# Modulo_MotorDC.net
KiCad netlist of a schematic drawn in Altium Designer
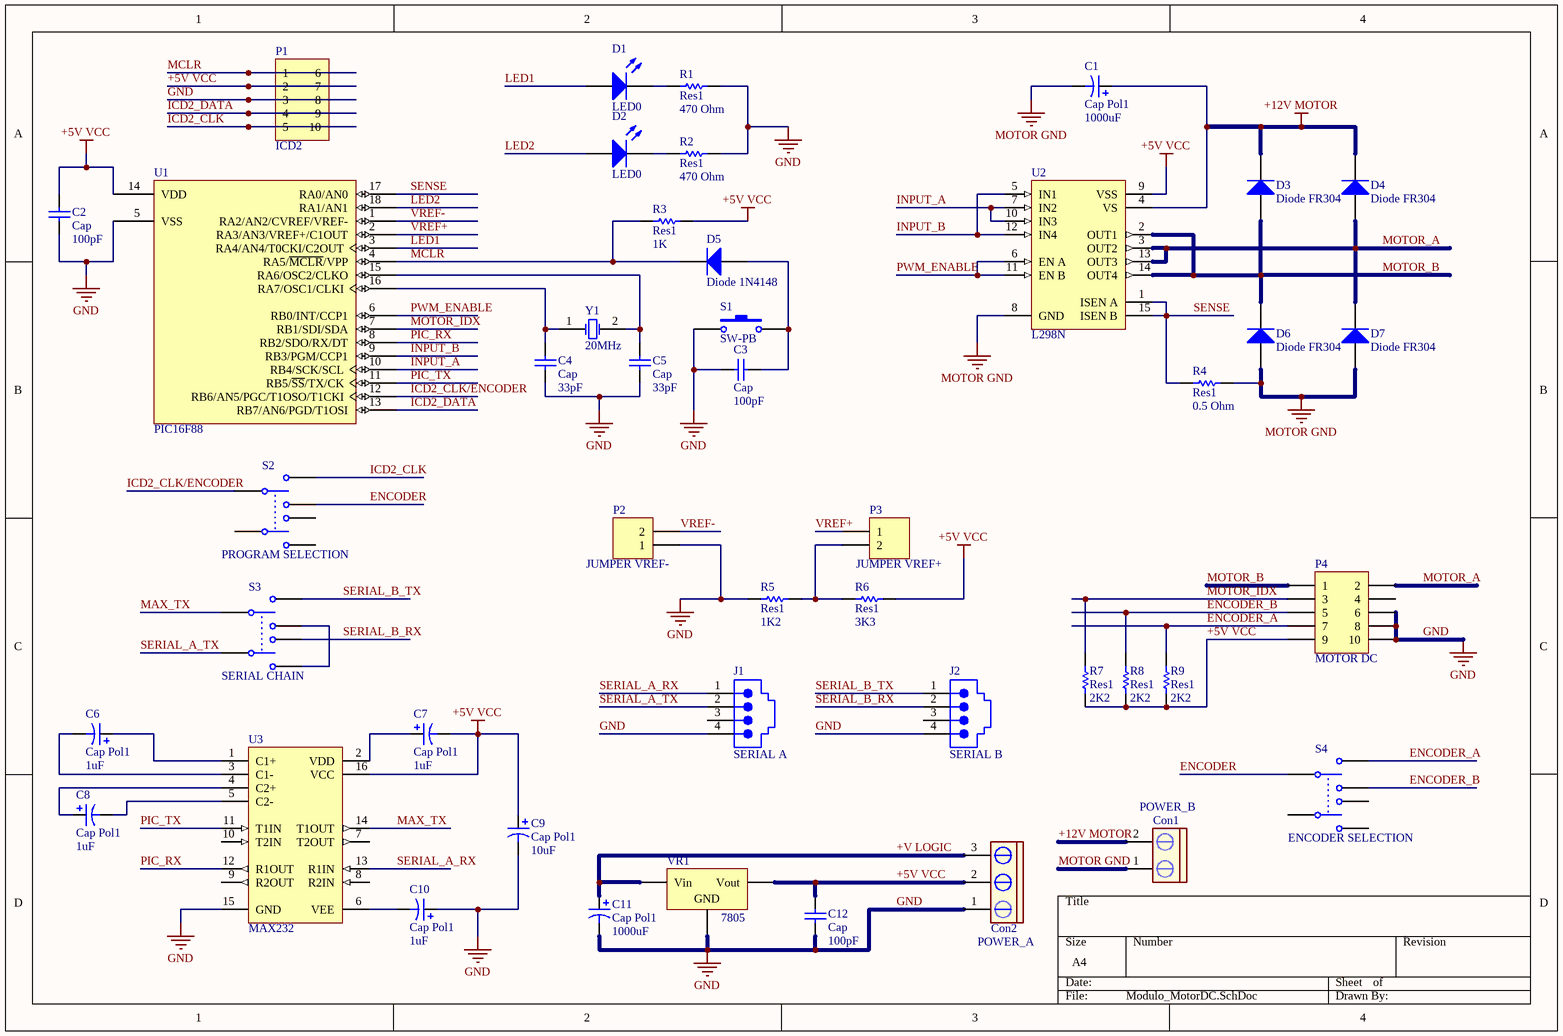
[diagram p0: Modulo_MotorDC.SchDoc]

(export (version "E")
  (design (tool "Eeschema 10.0.6"))
  (components
    (comp (ref "C1")
      (value "Cap Pol1")
      (footprint "RB5-10.5")
      (description "Polarized Capacitor (Radial)")
      (fields (field (name "ALTIUM_VALUE") "1000uF") (field (name "PUBLISHER") "Altium Limited"))
      (libsource (lib "Miscellaneous Devices") (part "Cap Pol1"))
    )
    (comp (ref "C2")
      (value "Cap")
      (footprint "CAPR2.54-5.1x3.2")
      (description "Capacitor")
      (fields (field (name "ALTIUM_VALUE") "100pF") (field (name "PUBLISHER") "Altium Limited"))
      (libsource (lib "Miscellaneous Devices") (part "Cap"))
    )
    (comp (ref "C3")
      (value "Cap")
      (footprint "CAPR2.54-5.1x3.2")
      (description "Capacitor")
      (fields (field (name "ALTIUM_VALUE") "100pF") (field (name "PUBLISHER") "Altium Limited"))
      (libsource (lib "Miscellaneous Devices") (part "Cap"))
    )
    (comp (ref "C4")
      (value "Cap")
      (footprint "CAPR2.54-5.1x3.2")
      (description "Capacitor")
      (fields (field (name "ALTIUM_VALUE") "33pF") (field (name "PUBLISHER") "Altium Limited"))
      (libsource (lib "Miscellaneous Devices") (part "Cap"))
    )
    (comp (ref "C5")
      (value "Cap")
      (footprint "CAPR2.54-5.1x3.2")
      (description "Capacitor")
      (fields (field (name "ALTIUM_VALUE") "33pF") (field (name "PUBLISHER") "Altium Limited"))
      (libsource (lib "Miscellaneous Devices") (part "Cap"))
    )
    (comp (ref "C6")
      (value "Cap Pol1")
      (footprint "CAPPR2-5x6.8")
      (description "Polarized Capacitor (Radial)")
      (fields (field (name "ALTIUM_VALUE") "1uF") (field (name "PUBLISHER") "Altium Limited"))
      (libsource (lib "Miscellaneous Devices") (part "Cap Pol1"))
    )
    (comp (ref "C7")
      (value "Cap Pol1")
      (footprint "CAPPR2-5x6.8")
      (description "Polarized Capacitor (Radial)")
      (fields (field (name "ALTIUM_VALUE") "1uF") (field (name "PUBLISHER") "Altium Limited"))
      (libsource (lib "Miscellaneous Devices") (part "Cap Pol1"))
    )
    (comp (ref "C8")
      (value "Cap Pol1")
      (footprint "CAPPR2-5x6.8")
      (description "Polarized Capacitor (Radial)")
      (fields (field (name "ALTIUM_VALUE") "1uF") (field (name "PUBLISHER") "Altium Limited"))
      (libsource (lib "Miscellaneous Devices") (part "Cap Pol1"))
    )
    (comp (ref "C9")
      (value "Cap Pol1")
      (footprint "CAPPR2-5x6.8")
      (description "Polarized Capacitor (Radial)")
      (fields (field (name "ALTIUM_VALUE") "10uF") (field (name "PUBLISHER") "Altium Limited"))
      (libsource (lib "Miscellaneous Devices") (part "Cap Pol1"))
    )
    (comp (ref "C10")
      (value "Cap Pol1")
      (footprint "CAPPR2-5x6.8")
      (description "Polarized Capacitor (Radial)")
      (fields (field (name "ALTIUM_VALUE") "1uF") (field (name "PUBLISHER") "Altium Limited"))
      (libsource (lib "Miscellaneous Devices") (part "Cap Pol1"))
    )
    (comp (ref "C11")
      (value "Cap Pol1")
      (footprint "RB5-10.5")
      (description "Polarized Capacitor (Radial)")
      (fields (field (name "ALTIUM_VALUE") "1000uF") (field (name "PUBLISHER") "Altium Limited"))
      (libsource (lib "Miscellaneous Devices") (part "Cap Pol1"))
    )
    (comp (ref "C12")
      (value "Cap")
      (footprint "CAPR2.54-5.1x3.2")
      (description "Capacitor")
      (fields (field (name "ALTIUM_VALUE") "100pF") (field (name "PUBLISHER") "Altium Limited"))
      (libsource (lib "Miscellaneous Devices") (part "Cap"))
    )
    (comp (ref "Con1")
      (value "POWER_B")
      (footprint "My_CN2")
      (description "Connector blue screw")
      (libsource (lib "Protel_Library") (part "CON2 pin blue"))
    )
    (comp (ref "Con2")
      (value "POWER_A")
      (footprint "My_CN3")
      (description "Connector green screw")
      (libsource (lib "Protel_Library") (part "CON3 pin Green"))
    )
    (comp (ref "D1")
      (value "LED0")
      (footprint "LED-0")
      (description "Typical INFRARED GaAs LED")
      (fields (field (name "PUBLISHER") "Altium Limited"))
      (libsource (lib "Miscellaneous Devices") (part "LED0"))
    )
    (comp (ref "D2")
      (value "LED0")
      (footprint "LED-0")
      (description "Typical INFRARED GaAs LED")
      (fields (field (name "PUBLISHER") "Altium Limited"))
      (libsource (lib "Miscellaneous Devices") (part "LED0"))
    )
    (comp (ref "D3")
      (value "Diode FR304")
      (footprint "DIO18.84-9.6x5.6")
      (description "3 Amp General Purpose Rectifier")
      (fields (field (name "PUBLISHER") "Altium Limited"))
      (libsource (lib "Miscellaneous Devices") (part "Diode 1N5404"))
    )
    (comp (ref "D4")
      (value "Diode FR304")
      (footprint "DIO18.84-9.6x5.6")
      (description "3 Amp General Purpose Rectifier")
      (fields (field (name "PUBLISHER") "Altium Limited"))
      (libsource (lib "Miscellaneous Devices") (part "Diode 1N5404"))
    )
    (comp (ref "D5")
      (value "Diode 1N4148")
      (footprint "DIO7.1-3.9x1.9")
      (description "High Conductance Fast Diode")
      (fields (field (name "PUBLISHER") "Altium Limited"))
      (libsource (lib "Miscellaneous Devices") (part "Diode 1N4148"))
    )
    (comp (ref "D6")
      (value "Diode FR304")
      (footprint "DIO18.84-9.6x5.6")
      (description "3 Amp General Purpose Rectifier")
      (fields (field (name "PUBLISHER") "Altium Limited"))
      (libsource (lib "Miscellaneous Devices") (part "Diode 1N5404"))
    )
    (comp (ref "D7")
      (value "Diode FR304")
      (footprint "DIO18.84-9.6x5.6")
      (description "3 Amp General Purpose Rectifier")
      (fields (field (name "PUBLISHER") "Altium Limited"))
      (libsource (lib "Miscellaneous Devices") (part "Diode 1N5404"))
    )
    (comp (ref "J1")
      (value "SERIAL A")
      (footprint "15-43-6245")
      (description "Right Angle, Standard Profile, RJ45-Keyed, Flange Mount PCB Jack")
      (fields (field (name "PUBLISHER") "Altium Limited"))
      (libsource (lib "Molex Modular Jack Right Angle") (part "15-43-6245"))
    )
    (comp (ref "J2")
      (value "SERIAL B")
      (footprint "15-43-6245")
      (description "Right Angle, Standard Profile, RJ45-Keyed, Flange Mount PCB Jack")
      (fields (field (name "PUBLISHER") "Altium Limited"))
      (libsource (lib "Molex Modular Jack Right Angle") (part "15-43-6245"))
    )
    (comp (ref "P1")
      (value "ICD2")
      (footprint "HEADER10_5x2_B")
      (description "Header, 5-Pin, Dual row")
      (fields (field (name "PUBLISHER") "Altium Limited"))
      (libsource (lib "Miscellaneous Connectors") (part "Header 5X2A"))
    )
    (comp (ref "P2")
      (value "JUMPER VREF-")
      (footprint "HDR1X2")
      (description "Header, 2-Pin")
      (fields (field (name "PUBLISHER") "Altium Limited"))
      (libsource (lib "Miscellaneous Connectors") (part "Header 2"))
    )
    (comp (ref "P3")
      (value "JUMPER VREF+")
      (footprint "HDR1X2")
      (description "Header, 2-Pin")
      (fields (field (name "PUBLISHER") "Altium Limited"))
      (libsource (lib "") (part "Header 2_1"))
    )
    (comp (ref "P4")
      (value "MOTOR DC")
      (footprint "HEADER10_5x2_A")
      (description "Header, 5-Pin, Dual row")
      (fields (field (name "PUBLISHER") "Altium Limited"))
      (libsource (lib "Miscellaneous Connectors") (part "Header 5X2"))
    )
    (comp (ref "R1")
      (value "Res1")
      (footprint "AXIAL-0.3")
      (description "Resistor")
      (fields (field (name "ALTIUM_VALUE") "470 Ohm") (field (name "PUBLISHER") "Altium Limited"))
      (libsource (lib "Miscellaneous Devices") (part "Res1"))
    )
    (comp (ref "R2")
      (value "Res1")
      (footprint "AXIAL-0.3")
      (description "Resistor")
      (fields (field (name "ALTIUM_VALUE") "470 Ohm") (field (name "PUBLISHER") "Altium Limited"))
      (libsource (lib "Miscellaneous Devices") (part "Res1"))
    )
    (comp (ref "R3")
      (value "Res1")
      (footprint "AXIAL-0.3")
      (description "Resistor")
      (fields (field (name "ALTIUM_VALUE") "1K") (field (name "PUBLISHER") "Altium Limited"))
      (libsource (lib "Miscellaneous Devices") (part "Res1"))
    )
    (comp (ref "R4")
      (value "Res1")
      (footprint "AXIAL-0.3")
      (description "Resistor")
      (fields (field (name "ALTIUM_VALUE") "0.5 Ohm") (field (name "PUBLISHER") "Altium Limited"))
      (libsource (lib "Miscellaneous Devices") (part "Res1"))
    )
    (comp (ref "R5")
      (value "Res1")
      (footprint "AXIAL-0.3")
      (description "Resistor")
      (fields (field (name "ALTIUM_VALUE") "1K2") (field (name "PUBLISHER") "Altium Limited"))
      (libsource (lib "Miscellaneous Devices") (part "Res1"))
    )
    (comp (ref "R6")
      (value "Res1")
      (footprint "AXIAL-0.3")
      (description "Resistor")
      (fields (field (name "ALTIUM_VALUE") "3K3") (field (name "PUBLISHER") "Altium Limited"))
      (libsource (lib "Miscellaneous Devices") (part "Res1"))
    )
    (comp (ref "R7")
      (value "Res1")
      (footprint "AXIAL-0.3")
      (description "Resistor")
      (fields (field (name "ALTIUM_VALUE") "2K2") (field (name "PUBLISHER") "Altium Limited"))
      (libsource (lib "Miscellaneous Devices") (part "Res1"))
    )
    (comp (ref "R8")
      (value "Res1")
      (footprint "AXIAL-0.3")
      (description "Resistor")
      (fields (field (name "ALTIUM_VALUE") "2K2") (field (name "PUBLISHER") "Altium Limited"))
      (libsource (lib "Miscellaneous Devices") (part "Res1"))
    )
    (comp (ref "R9")
      (value "Res1")
      (footprint "AXIAL-0.3")
      (description "Resistor")
      (fields (field (name "ALTIUM_VALUE") "2K2") (field (name "PUBLISHER") "Altium Limited"))
      (libsource (lib "Miscellaneous Devices") (part "Res1"))
    )
    (comp (ref "S1")
      (value "SW-PB")
      (footprint "TS-063")
      (description "Switch")
      (fields (field (name "PUBLISHER") "Altium Limited"))
      (libsource (lib "Miscellaneous Devices") (part "SW-PB"))
    )
    (comp (ref "S2")
      (value "PROGRAM SELECTION")
      (footprint "LD-202mini")
      (description "Double-Pole, Double-Throw Switch")
      (fields (field (name "PUBLISHER") "Altium Limited"))
      (libsource (lib "Miscellaneous Devices") (part "SW-DPDT"))
    )
    (comp (ref "S3")
      (value "SERIAL CHAIN")
      (footprint "LD-202mini")
      (description "Double-Pole, Double-Throw Switch")
      (fields (field (name "PUBLISHER") "Altium Limited"))
      (libsource (lib "Miscellaneous Devices") (part "SW-DPDT"))
    )
    (comp (ref "S4")
      (value "ENCODER SELECTION")
      (footprint "LD-202mini")
      (description "Double-Pole, Double-Throw Switch")
      (fields (field (name "PUBLISHER") "Altium Limited"))
      (libsource (lib "Miscellaneous Devices") (part "SW-DPDT"))
    )
    (comp (ref "U1")
      (value "PIC16F88")
      (footprint "PDIP300-P18")
      (fields (field (name "PUBLISHER") "Altium Limited"))
      (libsource (lib "Microchip Microcontroller 8-Bit PIC16") (part "PIC16F88-E/P"))
    )
    (comp (ref "U2")
      (value "L298N")
      (footprint "Multiwatt15V")
      (description "Dual Full Bridge Driver")
      (fields (field (name "PUBLISHER") "Altium Limited"))
      (libsource (lib "ST Interface DC Motor Controller") (part "L298N"))
    )
    (comp (ref "U3")
      (value "MAX232")
      (footprint "PE16A")
      (description "+5V Powered, Multi-Channel RS-232 Driver/Receiver")
      (fields (field (name "PUBLISHER") "Altium Limited"))
      (libsource (lib "Maxim Communication Transceiver") (part "MAX232ACPE"))
    )
    (comp (ref "VR1")
      (value "7805")
      (footprint "My_TO-220")
      (description "Voltage Regulator")
      (fields (field (name "PUBLISHER") "Altium Limited"))
      (libsource (lib "Miscellaneous Devices") (part "Volt Reg"))
    )
    (comp (ref "Y1")
      (value "20MHz")
      (footprint "My_Crystal")
      (description "Crystal Oscillator")
      (fields (field (name "PUBLISHER") "Altium Limited"))
      (libsource (lib "Miscellaneous Devices") (part "XTAL"))
    )
  )
  (nets
    (net (code "1") (name "+5V VCC") (class "Default")
      (node (ref "C12") (pin "2") (pinfunction "2_2") (pintype "passive"))
      (node (ref "C2") (pin "2") (pinfunction "2_2") (pintype "passive"))
      (node (ref "C7") (pin "2") (pinfunction "2_2") (pintype "passive"))
      (node (ref "C9") (pin "1") (pinfunction "1_1") (pintype "passive"))
      (node (ref "Con2") (pin "2") (pinfunction "2_2") (pintype "passive"))
      (node (ref "P1") (pin "2") (pinfunction "2_2") (pintype "passive"))
      (node (ref "P1") (pin "7") (pinfunction "7_7") (pintype "passive"))
      (node (ref "P4") (pin "9") (pinfunction "9_9") (pintype "passive"))
      (node (ref "R3") (pin "2") (pinfunction "2_2") (pintype "passive"))
      (node (ref "R6") (pin "2") (pinfunction "2_2") (pintype "passive"))
      (node (ref "R7") (pin "1") (pinfunction "1_1") (pintype "passive"))
      (node (ref "R8") (pin "1") (pinfunction "1_1") (pintype "passive"))
      (node (ref "R9") (pin "1") (pinfunction "1_1") (pintype "passive"))
      (node (ref "U1") (pin "14") (pinfunction "VDD_14") (pintype "power_in"))
      (node (ref "U2") (pin "9") (pinfunction "VSS_9") (pintype "power_in"))
      (node (ref "U3") (pin "16") (pinfunction "VCC_16") (pintype "power_in"))
      (node (ref "VR1") (pin "3") (pinfunction "Vout_3") (pintype "passive"))
    )
    (net (code "2") (name "+12V MOTOR") (class "Default")
      (node (ref "C1") (pin "1") (pinfunction "1_1") (pintype "passive"))
      (node (ref "Con1") (pin "2") (pinfunction "2_2") (pintype "passive"))
      (node (ref "D3") (pin "2") (pinfunction "K_2") (pintype "passive"))
      (node (ref "D4") (pin "2") (pinfunction "K_2") (pintype "passive"))
      (node (ref "U2") (pin "4") (pinfunction "VS_4") (pintype "power_in"))
    )
    (net (code "3") (name "/+V LOGIC") (class "Default")
      (node (ref "C11") (pin "1") (pinfunction "1_1") (pintype "passive"))
      (node (ref "Con2") (pin "3") (pinfunction "3_3") (pintype "passive"))
      (node (ref "VR1") (pin "1") (pinfunction "Vin_1") (pintype "passive"))
    )
    (net (code "5") (name "/ENCODER") (class "Default")
      (node (ref "S2") (pin "3") (pinfunction "3_3") (pintype "passive"))
      (node (ref "S4") (pin "1") (pinfunction "1_1") (pintype "passive"))
    )
    (net (code "6") (name "/ENCODER_A") (class "Default")
      (node (ref "P4") (pin "7") (pinfunction "7_7") (pintype "passive"))
      (node (ref "R9") (pin "2") (pinfunction "2_2") (pintype "passive"))
      (node (ref "S4") (pin "2") (pinfunction "2_2") (pintype "passive"))
    )
    (net (code "7") (name "/ENCODER_B") (class "Default")
      (node (ref "P4") (pin "5") (pinfunction "5_5") (pintype "passive"))
      (node (ref "R8") (pin "2") (pinfunction "2_2") (pintype "passive"))
      (node (ref "S4") (pin "3") (pinfunction "3_3") (pintype "passive"))
    )
    (net (code "8") (name "/ICD2_CLK") (class "Default")
      (node (ref "P1") (pin "10") (pinfunction "10_10") (pintype "passive"))
      (node (ref "P1") (pin "5") (pinfunction "5_5") (pintype "passive"))
      (node (ref "S2") (pin "2") (pinfunction "2_2") (pintype "passive"))
    )
    (net (code "9") (name "/ICD2_CLK{slash}ENCODER") (class "Default")
      (node (ref "S2") (pin "1") (pinfunction "1_1") (pintype "passive"))
      (node (ref "U1") (pin "12") (pinfunction "RB6/AN5/PGC/T1OSO/T1CKI_12") (pintype "bidirectional"))
    )
    (net (code "10") (name "/ICD2_DATA") (class "Default")
      (node (ref "P1") (pin "4") (pinfunction "4_4") (pintype "passive"))
      (node (ref "P1") (pin "9") (pinfunction "9_9") (pintype "passive"))
      (node (ref "U1") (pin "13") (pinfunction "RB7/AN6/PGD/T1OSI_13") (pintype "bidirectional"))
    )
    (net (code "11") (name "/INPUT_A") (class "Default")
      (node (ref "U1") (pin "10") (pinfunction "RB4/SCK/SCL_10") (pintype "bidirectional"))
      (node (ref "U2") (pin "10") (pinfunction "IN3_10") (pintype "input"))
      (node (ref "U2") (pin "7") (pinfunction "IN2_7") (pintype "input"))
    )
    (net (code "12") (name "/INPUT_B") (class "Default")
      (node (ref "U1") (pin "9") (pinfunction "RB3/PGM/CCP1_9") (pintype "bidirectional"))
      (node (ref "U2") (pin "12") (pinfunction "IN4_12") (pintype "input"))
      (node (ref "U2") (pin "5") (pinfunction "IN1_5") (pintype "input"))
    )
    (net (code "13") (name "/LED1") (class "Default")
      (node (ref "D1") (pin "1") (pinfunction "A_1") (pintype "passive"))
      (node (ref "U1") (pin "3") (pinfunction "RA4/AN4/T0CKI/C2OUT_3") (pintype "bidirectional"))
    )
    (net (code "14") (name "/LED2") (class "Default")
      (node (ref "D2") (pin "1") (pinfunction "A_1") (pintype "passive"))
      (node (ref "U1") (pin "18") (pinfunction "RA1/AN1_18") (pintype "bidirectional"))
    )
    (net (code "15") (name "/MAX_TX") (class "Default")
      (node (ref "S3") (pin "1") (pinfunction "1_1") (pintype "passive"))
      (node (ref "U3") (pin "14") (pinfunction "T1OUT_14") (pintype "output"))
    )
    (net (code "16") (name "/MCLR") (class "Default")
      (node (ref "D5") (pin "2") (pinfunction "K_2") (pintype "passive"))
      (node (ref "P1") (pin "1") (pinfunction "1_1") (pintype "passive"))
      (node (ref "P1") (pin "6") (pinfunction "6_6") (pintype "passive"))
      (node (ref "R3") (pin "1") (pinfunction "1_1") (pintype "passive"))
      (node (ref "U1") (pin "4") (pinfunction "RA5/~{MCLR}/VPP_4") (pintype "bidirectional"))
    )
    (net (code "17") (name "/MOTOR_A") (class "Default")
      (node (ref "D4") (pin "1") (pinfunction "A_1") (pintype "passive"))
      (node (ref "D7") (pin "2") (pinfunction "K_2") (pintype "passive"))
      (node (ref "P4") (pin "2") (pinfunction "2_2") (pintype "passive"))
      (node (ref "U2") (pin "13") (pinfunction "OUT3_13") (pintype "output"))
      (node (ref "U2") (pin "3") (pinfunction "OUT2_3") (pintype "output"))
    )
    (net (code "18") (name "/MOTOR_B") (class "Default")
      (node (ref "D3") (pin "1") (pinfunction "A_1") (pintype "passive"))
      (node (ref "D6") (pin "2") (pinfunction "K_2") (pintype "passive"))
      (node (ref "P4") (pin "1") (pinfunction "1_1") (pintype "passive"))
      (node (ref "U2") (pin "14") (pinfunction "OUT4_14") (pintype "output"))
      (node (ref "U2") (pin "2") (pinfunction "OUT1_2") (pintype "output"))
    )
    (net (code "19") (name "/MOTOR_IDX") (class "Default")
      (node (ref "P4") (pin "3") (pinfunction "3_3") (pintype "passive"))
      (node (ref "R7") (pin "2") (pinfunction "2_2") (pintype "passive"))
      (node (ref "U1") (pin "7") (pinfunction "RB1/SDI/SDA_7") (pintype "bidirectional"))
    )
    (net (code "20") (name "/PIC_RX") (class "Default")
      (node (ref "U1") (pin "8") (pinfunction "RB2/SDO/RX/DT_8") (pintype "bidirectional"))
      (node (ref "U3") (pin "12") (pinfunction "R1OUT_12") (pintype "output"))
    )
    (net (code "21") (name "/PIC_TX") (class "Default")
      (node (ref "U1") (pin "11") (pinfunction "RB5/~{SS}/TX/CK_11") (pintype "bidirectional"))
      (node (ref "U3") (pin "11") (pinfunction "T1IN_11") (pintype "input"))
    )
    (net (code "22") (name "/PWM_ENABLE") (class "Default")
      (node (ref "U1") (pin "6") (pinfunction "RB0/INT/CCP1_6") (pintype "bidirectional"))
      (node (ref "U2") (pin "11") (pinfunction "EN_B_11") (pintype "input"))
      (node (ref "U2") (pin "6") (pinfunction "EN_A_6") (pintype "input"))
    )
    (net (code "23") (name "/SENSE") (class "Default")
      (node (ref "R4") (pin "1") (pinfunction "1_1") (pintype "passive"))
      (node (ref "U1") (pin "17") (pinfunction "RA0/AN0_17") (pintype "bidirectional"))
      (node (ref "U2") (pin "1") (pinfunction "ISEN_A_1") (pintype "passive"))
      (node (ref "U2") (pin "15") (pinfunction "ISEN_B_15") (pintype "passive"))
    )
    (net (code "24") (name "/SERIAL_A_RX") (class "Default")
      (node (ref "J1") (pin "1") (pinfunction "1_1") (pintype "passive"))
      (node (ref "U3") (pin "13") (pinfunction "R1IN_13") (pintype "input"))
    )
    (net (code "25") (name "/SERIAL_A_TX") (class "Default")
      (node (ref "J1") (pin "2") (pinfunction "2_2") (pintype "passive"))
      (node (ref "S3") (pin "4") (pinfunction "4_4") (pintype "passive"))
    )
    (net (code "26") (name "/SERIAL_B_RX") (class "Default")
      (node (ref "J2") (pin "2") (pinfunction "2_2") (pintype "passive"))
      (node (ref "S3") (pin "5") (pinfunction "5_5") (pintype "passive"))
    )
    (net (code "27") (name "/SERIAL_B_TX") (class "Default")
      (node (ref "J2") (pin "1") (pinfunction "1_1") (pintype "passive"))
      (node (ref "S3") (pin "2") (pinfunction "2_2") (pintype "passive"))
    )
    (net (code "28") (name "/VREF+") (class "Default")
      (node (ref "P3") (pin "1") (pinfunction "1_1") (pintype "passive"))
      (node (ref "U1") (pin "2") (pinfunction "RA3/AN3/VREF+/C1OUT_2") (pintype "bidirectional"))
    )
    (net (code "29") (name "/VREF-") (class "Default")
      (node (ref "P2") (pin "2") (pinfunction "2_2") (pintype "passive"))
      (node (ref "U1") (pin "1") (pinfunction "RA2/AN2/CVREF/VREF-_1") (pintype "bidirectional"))
    )
    (net (code "30") (name "GND") (class "Default")
      (node (ref "C10") (pin "1") (pinfunction "1_1") (pintype "passive"))
      (node (ref "C11") (pin "2") (pinfunction "2_2") (pintype "passive"))
      (node (ref "C12") (pin "1") (pinfunction "1_1") (pintype "passive"))
      (node (ref "C2") (pin "1") (pinfunction "1_1") (pintype "passive"))
      (node (ref "C3") (pin "1") (pinfunction "1_1") (pintype "passive"))
      (node (ref "C4") (pin "1") (pinfunction "1_1") (pintype "passive"))
      (node (ref "C5") (pin "1") (pinfunction "1_1") (pintype "passive"))
      (node (ref "C9") (pin "2") (pinfunction "2_2") (pintype "passive"))
      (node (ref "Con2") (pin "1") (pinfunction "1_1") (pintype "passive"))
      (node (ref "J1") (pin "4") (pinfunction "4_4") (pintype "passive"))
      (node (ref "J2") (pin "4") (pinfunction "4_4") (pintype "passive"))
      (node (ref "P1") (pin "3") (pinfunction "3_3") (pintype "passive"))
      (node (ref "P1") (pin "8") (pinfunction "8_8") (pintype "passive"))
      (node (ref "P2") (pin "1") (pinfunction "1_1") (pintype "passive"))
      (node (ref "P4") (pin "10") (pinfunction "10_10") (pintype "passive"))
      (node (ref "P4") (pin "6") (pinfunction "6_6") (pintype "passive"))
      (node (ref "P4") (pin "8") (pinfunction "8_8") (pintype "passive"))
      (node (ref "R1") (pin "2") (pinfunction "2_2") (pintype "passive"))
      (node (ref "R2") (pin "2") (pinfunction "2_2") (pintype "passive"))
      (node (ref "R5") (pin "1") (pinfunction "1_1") (pintype "passive"))
      (node (ref "S1") (pin "1") (pinfunction "1_1") (pintype "passive"))
      (node (ref "U1") (pin "5") (pinfunction "VSS_5") (pintype "power_in"))
      (node (ref "U3") (pin "15") (pinfunction "GND_15") (pintype "power_in"))
      (node (ref "VR1") (pin "2") (pinfunction "GND_2") (pintype "passive"))
    )
    (net (code "31") (name "MOTOR GND") (class "Default")
      (node (ref "C1") (pin "2") (pinfunction "2_2") (pintype "passive"))
      (node (ref "Con1") (pin "1") (pinfunction "1_1") (pintype "passive"))
      (node (ref "D6") (pin "1") (pinfunction "A_1") (pintype "passive"))
      (node (ref "D7") (pin "1") (pinfunction "A_1") (pintype "passive"))
      (node (ref "R4") (pin "2") (pinfunction "2_2") (pintype "passive"))
      (node (ref "U2") (pin "8") (pinfunction "GND_8") (pintype "power_in"))
    )
    (net (code "32") (name "Net-(D1-K)") (class "Default")
      (node (ref "D1") (pin "2") (pinfunction "K_2") (pintype "passive"))
      (node (ref "R1") (pin "1") (pinfunction "1_1") (pintype "passive"))
    )
    (net (code "33") (name "Net-(D2-K)") (class "Default")
      (node (ref "D2") (pin "2") (pinfunction "K_2") (pintype "passive"))
      (node (ref "R2") (pin "1") (pinfunction "1_1") (pintype "passive"))
    )
    (net (code "34") (name "Net-(D5-A)") (class "Default")
      (node (ref "C3") (pin "2") (pinfunction "2_2") (pintype "passive"))
      (node (ref "D5") (pin "1") (pinfunction "A_1") (pintype "passive"))
      (node (ref "S1") (pin "2") (pinfunction "2_2") (pintype "passive"))
    )
    (net (code "35") (name "Net-(P3-Pad2)") (class "Default")
      (node (ref "P3") (pin "2") (pinfunction "2_2") (pintype "passive"))
      (node (ref "R5") (pin "2") (pinfunction "2_2") (pintype "passive"))
      (node (ref "R6") (pin "1") (pinfunction "1_1") (pintype "passive"))
    )
    (net (code "36") (name "Net-(S3-Pad3)") (class "Default")
      (node (ref "S3") (pin "3") (pinfunction "3_3") (pintype "passive"))
      (node (ref "S3") (pin "6") (pinfunction "6_6") (pintype "passive"))
    )
    (net (code "37") (name "Net-(U1-RA6{slash}OSC2{slash}CLKO)") (class "Default")
      (node (ref "C5") (pin "2") (pinfunction "2_2") (pintype "passive"))
      (node (ref "U1") (pin "15") (pinfunction "RA6/OSC2/CLKO_15") (pintype "bidirectional"))
      (node (ref "Y1") (pin "2") (pinfunction "OSC2_2") (pintype "passive"))
    )
    (net (code "38") (name "Net-(U1-RA7{slash}OSC1{slash}CLKI)") (class "Default")
      (node (ref "C4") (pin "2") (pinfunction "2_2") (pintype "passive"))
      (node (ref "U1") (pin "16") (pinfunction "RA7/OSC1/CLKI_16") (pintype "bidirectional"))
      (node (ref "Y1") (pin "1") (pinfunction "OSC1_1") (pintype "passive"))
    )
    (net (code "39") (name "Net-(U3-C1+)") (class "Default")
      (node (ref "C6") (pin "1") (pinfunction "1_1") (pintype "passive"))
      (node (ref "U3") (pin "1") (pinfunction "C1+_1") (pintype "passive"))
    )
    (net (code "40") (name "Net-(U3-C1-)") (class "Default")
      (node (ref "C6") (pin "2") (pinfunction "2_2") (pintype "passive"))
      (node (ref "U3") (pin "3") (pinfunction "C1-_3") (pintype "passive"))
    )
    (net (code "41") (name "Net-(U3-C2+)") (class "Default")
      (node (ref "C8") (pin "1") (pinfunction "1_1") (pintype "passive"))
      (node (ref "U3") (pin "4") (pinfunction "C2+_4") (pintype "passive"))
    )
    (net (code "42") (name "Net-(U3-C2-)") (class "Default")
      (node (ref "C8") (pin "2") (pinfunction "2_2") (pintype "passive"))
      (node (ref "U3") (pin "5") (pinfunction "C2-_5") (pintype "passive"))
    )
    (net (code "43") (name "Net-(U3-VDD)") (class "Default")
      (node (ref "C7") (pin "1") (pinfunction "1_1") (pintype "passive"))
      (node (ref "U3") (pin "2") (pinfunction "VDD_2") (pintype "power_in"))
    )
    (net (code "44") (name "Net-(U3-VEE)") (class "Default")
      (node (ref "C10") (pin "2") (pinfunction "2_2") (pintype "passive"))
      (node (ref "U3") (pin "6") (pinfunction "VEE_6") (pintype "power_in"))
    )
    (net (code "45") (name "unconnected-(J1-Pad3)") (class "Default")
      (node (ref "J1") (pin "3") (pinfunction "3_3") (pintype "passive"))
    )
    (net (code "46") (name "unconnected-(J2-Pad3)") (class "Default")
      (node (ref "J2") (pin "3") (pinfunction "3_3") (pintype "passive"))
    )
    (net (code "47") (name "unconnected-(P4-Pad4)") (class "Default")
      (node (ref "P4") (pin "4") (pinfunction "4_4") (pintype "passive"))
    )
    (net (code "48") (name "unconnected-(S2-Pad4)") (class "Default")
      (node (ref "S2") (pin "4") (pinfunction "4_4") (pintype "passive"))
    )
    (net (code "49") (name "unconnected-(S2-Pad5)") (class "Default")
      (node (ref "S2") (pin "5") (pinfunction "5_5") (pintype "passive"))
    )
    (net (code "50") (name "unconnected-(S2-Pad6)") (class "Default")
      (node (ref "S2") (pin "6") (pinfunction "6_6") (pintype "passive"))
    )
    (net (code "51") (name "unconnected-(S4-Pad4)") (class "Default")
      (node (ref "S4") (pin "4") (pinfunction "4_4") (pintype "passive"))
    )
    (net (code "52") (name "unconnected-(S4-Pad5)") (class "Default")
      (node (ref "S4") (pin "5") (pinfunction "5_5") (pintype "passive"))
    )
    (net (code "53") (name "unconnected-(S4-Pad6)") (class "Default")
      (node (ref "S4") (pin "6") (pinfunction "6_6") (pintype "passive"))
    )
    (net (code "54") (name "unconnected-(U3-R2IN-Pad8)") (class "Default")
      (node (ref "U3") (pin "8") (pinfunction "R2IN_8") (pintype "input"))
    )
    (net (code "55") (name "unconnected-(U3-R2OUT-Pad9)") (class "Default")
      (node (ref "U3") (pin "9") (pinfunction "R2OUT_9") (pintype "output"))
    )
    (net (code "56") (name "unconnected-(U3-T2IN-Pad10)") (class "Default")
      (node (ref "U3") (pin "10") (pinfunction "T2IN_10") (pintype "input"))
    )
    (net (code "57") (name "unconnected-(U3-T2OUT-Pad7)") (class "Default")
      (node (ref "U3") (pin "7") (pinfunction "T2OUT_7") (pintype "output"))
    )
  )
)
